# dosimeter.net
KiCad netlist of a schematic drawn in EAGLE
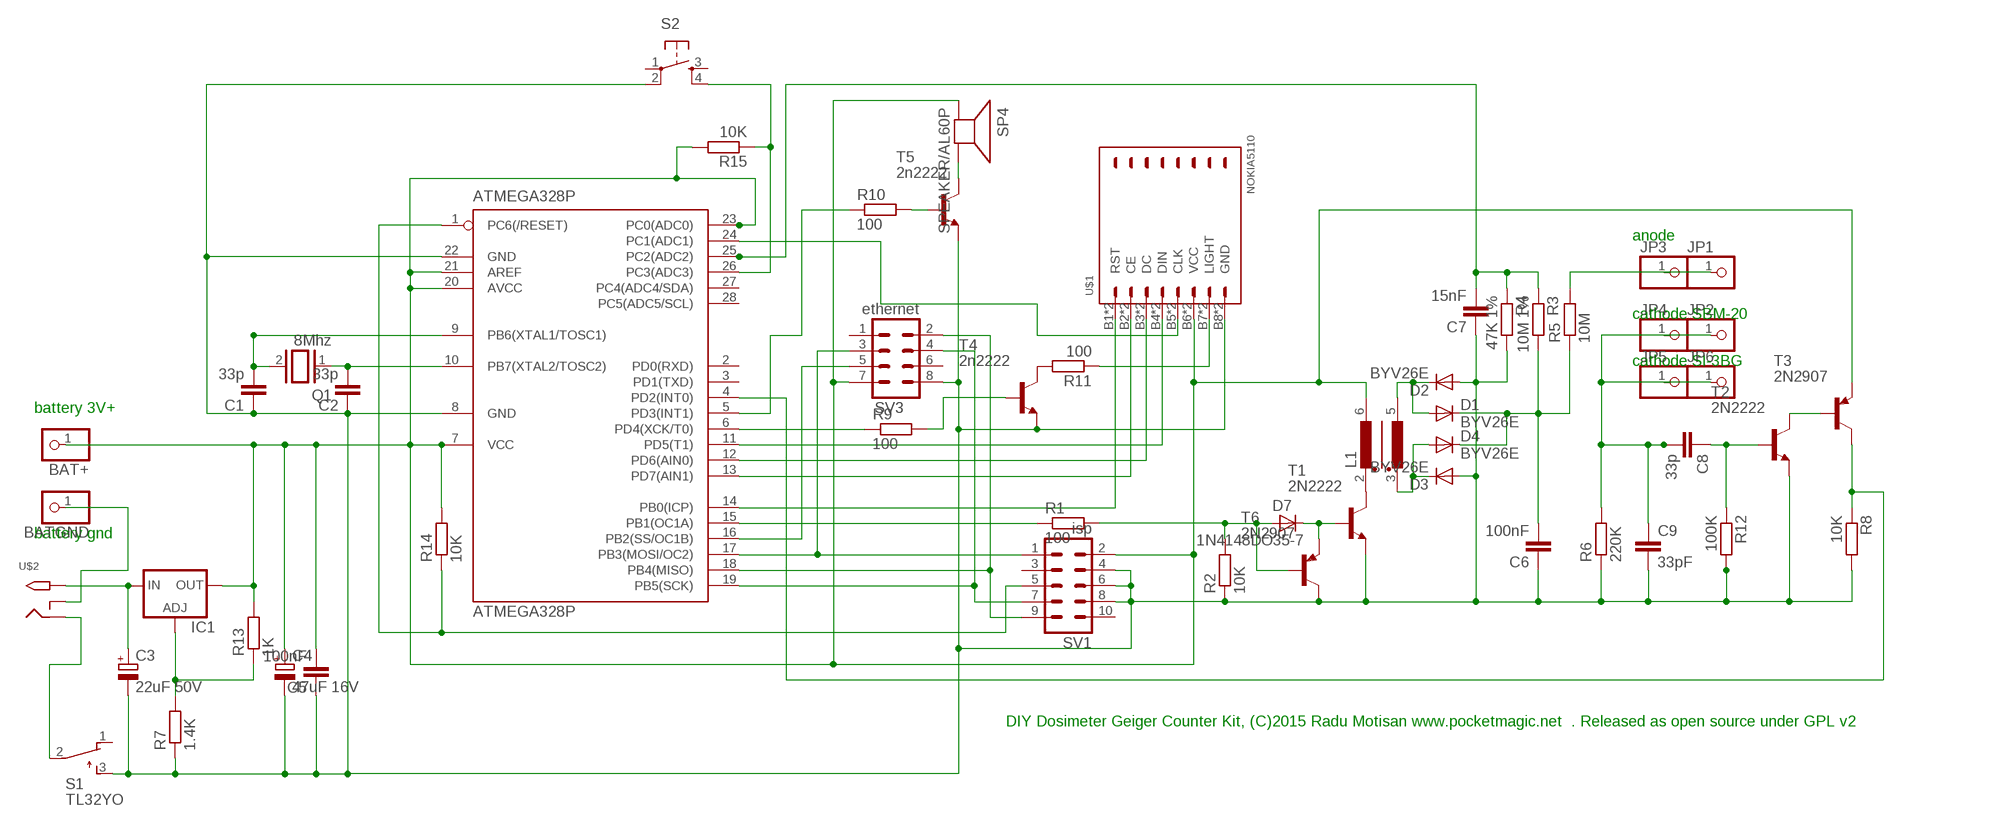
[diagram p0: schematic, sheet 1]

(export (version "E")
  (design (tool "Eeschema 10.0.6"))
  (components
    (comp (ref "ATMEGA328P")
      (value "ATMEGA328P")
      (footprint "eagle-import:DIL28-3")
      (libsource (lib "eagle-import") (part "MEGA8-P"))
    )
    (comp (ref "BAT+")
      (value "PINHD-1X1")
      (footprint "eagle-import:1X01")
      (libsource (lib "eagle-import") (part "PINHD-1X1"))
    )
    (comp (ref "BATGND")
      (value "PINHD-1X1")
      (footprint "eagle-import:1X01")
      (libsource (lib "eagle-import") (part "PINHD-1X1"))
    )
    (comp (ref "C1")
      (value "33p")
      (footprint "eagle-import:C2.5-2")
      (libsource (lib "eagle-import") (part "C2.5/2"))
    )
    (comp (ref "C2")
      (value "33p")
      (footprint "eagle-import:C2.5-2")
      (libsource (lib "eagle-import") (part "C2.5/2"))
    )
    (comp (ref "C3")
      (value "22uF 50V")
      (footprint "eagle-import:E2-5")
      (libsource (lib "eagle-import") (part "CPOL-EUE2-5"))
    )
    (comp (ref "C4")
      (value "47uF 16V")
      (footprint "eagle-import:E2-5")
      (libsource (lib "eagle-import") (part "CPOL-EUE2-5"))
    )
    (comp (ref "C5")
      (value "100nF")
      (footprint "eagle-import:C2.5-2")
      (libsource (lib "eagle-import") (part "C2.5/2"))
    )
    (comp (ref "C6")
      (value "100nF")
      (footprint "eagle-import:C5B3")
      (libsource (lib "eagle-import") (part "C5/3"))
    )
    (comp (ref "C7")
      (value "15nF")
      (footprint "eagle-import:C2.5-2")
      (libsource (lib "eagle-import") (part "C2.5/2"))
    )
    (comp (ref "C8")
      (value "33p")
      (footprint "eagle-import:C2.5-2")
      (libsource (lib "eagle-import") (part "C2.5/2"))
    )
    (comp (ref "C9")
      (value "33pF")
      (footprint "eagle-import:C2.5-2")
      (libsource (lib "eagle-import") (part "C2.5/2"))
    )
    (comp (ref "D1")
      (value "BYV26E")
      (footprint "eagle-import:D-7.5")
      (libsource (lib "eagle-import") (part "1N40047.5"))
    )
    (comp (ref "D2")
      (value "BYV26E")
      (footprint "eagle-import:D-7.5")
      (libsource (lib "eagle-import") (part "1N40047.5"))
    )
    (comp (ref "D3")
      (value "BYV26E")
      (footprint "eagle-import:D-7.5")
      (libsource (lib "eagle-import") (part "1N40047.5"))
    )
    (comp (ref "D4")
      (value "BYV26E")
      (footprint "eagle-import:D-7.5")
      (libsource (lib "eagle-import") (part "1N40047.5"))
    )
    (comp (ref "D7")
      (value "1N4148DO35-7")
      (footprint "eagle-import:DO35-7")
      (libsource (lib "eagle-import") (part "1N4148DO35-7"))
    )
    (comp (ref "IC1")
      (value "LM317TL")
      (footprint "eagle-import:317TL")
      (libsource (lib "eagle-import") (part "LM317TL"))
    )
    (comp (ref "JP1")
      (value "PINHD-1X1")
      (footprint "eagle-import:1X01")
      (libsource (lib "eagle-import") (part "PINHD-1X1"))
    )
    (comp (ref "JP2")
      (value "PINHD-1X1")
      (footprint "eagle-import:1X01")
      (libsource (lib "eagle-import") (part "PINHD-1X1"))
    )
    (comp (ref "JP3")
      (value "PINHD-1X1")
      (footprint "eagle-import:1X01")
      (libsource (lib "eagle-import") (part "PINHD-1X1"))
    )
    (comp (ref "JP4")
      (value "PINHD-1X1")
      (footprint "eagle-import:1X01")
      (libsource (lib "eagle-import") (part "PINHD-1X1"))
    )
    (comp (ref "JP5")
      (value "PINHD-1X1")
      (footprint "eagle-import:1X01")
      (libsource (lib "eagle-import") (part "PINHD-1X1"))
    )
    (comp (ref "JP6")
      (value "PINHD-1X1")
      (footprint "eagle-import:1X01")
      (libsource (lib "eagle-import") (part "PINHD-1X1"))
    )
    (comp (ref "L1")
      (value "RM6-2")
      (footprint "eagle-import:RM5-4")
      (libsource (lib "eagle-import") (part "RM6-2"))
    )
    (comp (ref "Q1")
      (value "8Mhz")
      (footprint "eagle-import:QS")
      (libsource (lib "eagle-import") (part "XTAL/S"))
    )
    (comp (ref "R1")
      (value "100")
      (footprint "eagle-import:0204_7")
      (libsource (lib "eagle-import") (part "R-EU_0204/7"))
    )
    (comp (ref "R2")
      (value "10K")
      (footprint "eagle-import:0204_7")
      (libsource (lib "eagle-import") (part "R-EU_0204/7"))
    )
    (comp (ref "R3")
      (value "10M 1%")
      (footprint "eagle-import:0204_7")
      (libsource (lib "eagle-import") (part "R-EU_0204/7"))
    )
    (comp (ref "R4")
      (value "47K 1%")
      (footprint "eagle-import:0204_7")
      (libsource (lib "eagle-import") (part "R-EU_0204/7"))
    )
    (comp (ref "R5")
      (value "10M")
      (footprint "eagle-import:0204_7")
      (libsource (lib "eagle-import") (part "R-EU_0204/7"))
    )
    (comp (ref "R6")
      (value "220K")
      (footprint "eagle-import:0204_7")
      (libsource (lib "eagle-import") (part "R-EU_0204/7"))
    )
    (comp (ref "R7")
      (value "1.4K")
      (footprint "eagle-import:0204_7")
      (libsource (lib "eagle-import") (part "R-EU_0204/7"))
    )
    (comp (ref "R8")
      (value "10K")
      (footprint "eagle-import:0204_7")
      (libsource (lib "eagle-import") (part "R-EU_0204/7"))
    )
    (comp (ref "R9")
      (value "100")
      (footprint "eagle-import:0204_7")
      (libsource (lib "eagle-import") (part "R-EU_0204/7"))
    )
    (comp (ref "R10")
      (value "100")
      (footprint "eagle-import:0204_7")
      (libsource (lib "eagle-import") (part "R-EU_0204/7"))
    )
    (comp (ref "R11")
      (value "100")
      (footprint "eagle-import:0204_7")
      (libsource (lib "eagle-import") (part "R-EU_0204/7"))
    )
    (comp (ref "R12")
      (value "100K")
      (footprint "eagle-import:0204_7")
      (libsource (lib "eagle-import") (part "R-EU_0204/7"))
    )
    (comp (ref "R13")
      (value "1K")
      (footprint "eagle-import:0204_7")
      (libsource (lib "eagle-import") (part "R-EU_0204/7"))
    )
    (comp (ref "R14")
      (value "10K")
      (footprint "eagle-import:0204_7")
      (libsource (lib "eagle-import") (part "R-EU_0204/7"))
    )
    (comp (ref "R15")
      (value "10K")
      (footprint "eagle-import:0204_7")
      (libsource (lib "eagle-import") (part "R-EU_0204/7"))
    )
    (comp (ref "S1")
      (value "TL32YO")
      (footprint "eagle-import:TL3XYO")
      (libsource (lib "eagle-import") (part "TL32YO"))
    )
    (comp (ref "S2")
      (value "TAC_SWITCHPTH")
      (footprint "eagle-import:TACTILE-PTH")
      (libsource (lib "eagle-import") (part "TAC_SWITCHPTH"))
    )
    (comp (ref "SP4")
      (value "SPEAKER/AL60P")
      (footprint "eagle-import:AL60P")
      (libsource (lib "eagle-import") (part "SPEAKER/AL60P"))
    )
    (comp (ref "SV1")
      (value "isp")
      (footprint "eagle-import:MA05-2")
      (libsource (lib "eagle-import") (part "MA05-2"))
    )
    (comp (ref "SV3")
      (value "ethernet")
      (footprint "eagle-import:MA04-2")
      (libsource (lib "eagle-import") (part "MA04-2"))
    )
    (comp (ref "T1")
      (value "2N2222")
      (footprint "eagle-import:TO92-EBC-OVAL")
      (libsource (lib "eagle-import") (part "2N2222"))
    )
    (comp (ref "T2")
      (value "2N2222")
      (footprint "eagle-import:TO92-EBC-OVAL")
      (libsource (lib "eagle-import") (part "2N2222"))
    )
    (comp (ref "T3")
      (value "2N2907")
      (footprint "eagle-import:TO92-EBC-OVAL")
      (libsource (lib "eagle-import") (part "2N2907"))
    )
    (comp (ref "T4")
      (value "2n2222")
      (footprint "eagle-import:TO92-EBC")
      (libsource (lib "eagle-import") (part "-NPN-TO92-EBC2N2222"))
    )
    (comp (ref "T5")
      (value "2n2222")
      (footprint "eagle-import:TO92-EBC")
      (libsource (lib "eagle-import") (part "-NPN-TO92-EBC2N2222"))
    )
    (comp (ref "T6")
      (value "2N2907")
      (footprint "eagle-import:TO92-EBC-OVAL")
      (libsource (lib "eagle-import") (part "2N2907"))
    )
    (comp (ref "U$1")
      (value "NOKIA5110")
      (footprint "eagle-import:NOKIA5110")
      (libsource (lib "eagle-import") (part "NOKIA5110"))
    )
    (comp (ref "U$2")
      (value "2.1MMJACKTHM")
      (footprint "eagle-import:PJ-102A")
      (libsource (lib "eagle-import") (part "2.1MMJACKTHM"))
    )
  )
  (nets
    (net (code "1") (name "Net-(ATMEGA328P-AREF)") (class "Default")
      (node (ref "ATMEGA328P") (pin "20") (pinfunction "AVCC_20") (pintype "power_in"))
      (node (ref "ATMEGA328P") (pin "21") (pinfunction "AREF_21") (pintype "passive"))
      (node (ref "ATMEGA328P") (pin "23") (pinfunction "PC0(ADC0)_23") (pintype "bidirectional"))
      (node (ref "ATMEGA328P") (pin "7") (pinfunction "VCC_7") (pintype "power_in"))
      (node (ref "BAT+") (pin "1") (pinfunction "1_1") (pintype "passive"))
      (node (ref "C4") (pin "+") (pinfunction "+_+") (pintype "passive"))
      (node (ref "C5") (pin "2") (pinfunction "2_2") (pintype "passive"))
      (node (ref "IC1") (pin "2") (pinfunction "OUT_2") (pintype "passive"))
      (node (ref "L1") (pin "6") (pinfunction "W1E_6") (pintype "passive"))
      (node (ref "R13") (pin "2") (pinfunction "2_2") (pintype "passive"))
      (node (ref "R14") (pin "2") (pinfunction "2_2") (pintype "passive"))
      (node (ref "R15") (pin "2") (pinfunction "2_2") (pintype "passive"))
      (node (ref "SP4") (pin "1") (pinfunction "+_1") (pintype "passive"))
      (node (ref "SV1") (pin "2") (pinfunction "2_2") (pintype "passive"))
      (node (ref "SV3") (pin "7") (pinfunction "7_7") (pintype "passive"))
      (node (ref "T3") (pin "E") (pinfunction "E_E") (pintype "passive"))
      (node (ref "U$1") (pin "B6") (pinfunction "VCC_B6") (pintype "bidirectional"))
      (node (ref "U$1") (pin "T6") (pinfunction "VCC_T6") (pintype "bidirectional"))
    )
    (net (code "2") (name "Net-(ATMEGA328P-PB0(ICP))") (class "Default")
      (node (ref "ATMEGA328P") (pin "14") (pinfunction "PB0(ICP)_14") (pintype "bidirectional"))
      (node (ref "U$1") (pin "B1") (pinfunction "RST_B1") (pintype "bidirectional"))
      (node (ref "U$1") (pin "T1") (pinfunction "RST_T1") (pintype "bidirectional"))
    )
    (net (code "3") (name "Net-(ATMEGA328P-PB1(OC1A))") (class "Default")
      (node (ref "ATMEGA328P") (pin "15") (pinfunction "PB1(OC1A)_15") (pintype "bidirectional"))
      (node (ref "R1") (pin "1") (pinfunction "1_1") (pintype "passive"))
    )
    (net (code "4") (name "Net-(ATMEGA328P-PB2(SS{slash}OC1B))") (class "Default")
      (node (ref "ATMEGA328P") (pin "16") (pinfunction "PB2(SS/OC1B)_16") (pintype "bidirectional"))
      (node (ref "SV3") (pin "5") (pinfunction "5_5") (pintype "passive"))
    )
    (net (code "5") (name "Net-(ATMEGA328P-PB3(MOSI{slash}OC2))") (class "Default")
      (node (ref "ATMEGA328P") (pin "17") (pinfunction "PB3(MOSI/OC2)_17") (pintype "bidirectional"))
      (node (ref "SV1") (pin "1") (pinfunction "1_1") (pintype "passive"))
      (node (ref "SV3") (pin "3") (pinfunction "3_3") (pintype "passive"))
    )
    (net (code "6") (name "Net-(ATMEGA328P-PB4(MISO))") (class "Default")
      (node (ref "ATMEGA328P") (pin "18") (pinfunction "PB4(MISO)_18") (pintype "bidirectional"))
      (node (ref "SV1") (pin "9") (pinfunction "9_9") (pintype "passive"))
      (node (ref "SV3") (pin "2") (pinfunction "2_2") (pintype "passive"))
    )
    (net (code "7") (name "Net-(ATMEGA328P-PB5(SCK))") (class "Default")
      (node (ref "ATMEGA328P") (pin "19") (pinfunction "PB5(SCK)_19") (pintype "bidirectional"))
      (node (ref "SV1") (pin "7") (pinfunction "7_7") (pintype "passive"))
      (node (ref "SV3") (pin "4") (pinfunction "4_4") (pintype "passive"))
    )
    (net (code "8") (name "Net-(ATMEGA328P-PB6(XTAL1{slash}TOSC1))") (class "Default")
      (node (ref "ATMEGA328P") (pin "9") (pinfunction "PB6(XTAL1/TOSC1)_9") (pintype "bidirectional"))
      (node (ref "C1") (pin "2") (pinfunction "2_2") (pintype "passive"))
      (node (ref "Q1") (pin "2") (pinfunction "2_2") (pintype "passive"))
    )
    (net (code "9") (name "Net-(ATMEGA328P-PB7(XTAL2{slash}TOSC2))") (class "Default")
      (node (ref "ATMEGA328P") (pin "10") (pinfunction "PB7(XTAL2/TOSC2)_10") (pintype "bidirectional"))
      (node (ref "C2") (pin "2") (pinfunction "2_2") (pintype "passive"))
      (node (ref "Q1") (pin "1") (pinfunction "1_1") (pintype "passive"))
    )
    (net (code "10") (name "Net-(ATMEGA328P-PC1(ADC1))") (class "Default")
      (node (ref "ATMEGA328P") (pin "24") (pinfunction "PC1(ADC1)_24") (pintype "bidirectional"))
      (node (ref "U$1") (pin "B5") (pinfunction "CLK_B5") (pintype "bidirectional"))
      (node (ref "U$1") (pin "T5") (pinfunction "CLK_T5") (pintype "bidirectional"))
    )
    (net (code "11") (name "Net-(ATMEGA328P-PC2(ADC2))") (class "Default")
      (node (ref "ATMEGA328P") (pin "25") (pinfunction "PC2(ADC2)_25") (pintype "bidirectional"))
      (node (ref "C7") (pin "2") (pinfunction "2_2") (pintype "passive"))
      (node (ref "R3") (pin "1") (pinfunction "1_1") (pintype "passive"))
      (node (ref "R4") (pin "1") (pinfunction "1_1") (pintype "passive"))
    )
    (net (code "12") (name "Net-(ATMEGA328P-PC3(ADC3))") (class "Default")
      (node (ref "ATMEGA328P") (pin "26") (pinfunction "PC3(ADC3)_26") (pintype "bidirectional"))
      (node (ref "R15") (pin "1") (pinfunction "1_1") (pintype "passive"))
      (node (ref "S2") (pin "4") (pinfunction "4_4") (pintype "passive"))
    )
    (net (code "13") (name "Net-(ATMEGA328P-PC6({slash}RESET))") (class "Default")
      (node (ref "ATMEGA328P") (pin "1") (pinfunction "PC6(/RESET)_1") (pintype "bidirectional"))
      (node (ref "R14") (pin "1") (pinfunction "1_1") (pintype "passive"))
      (node (ref "SV1") (pin "5") (pinfunction "5_5") (pintype "passive"))
    )
    (net (code "14") (name "Net-(ATMEGA328P-PD2(INT0))") (class "Default")
      (node (ref "ATMEGA328P") (pin "4") (pinfunction "PD2(INT0)_4") (pintype "bidirectional"))
      (node (ref "R8") (pin "1") (pinfunction "1_1") (pintype "passive"))
      (node (ref "T3") (pin "C") (pinfunction "C_C") (pintype "passive"))
    )
    (net (code "15") (name "Net-(ATMEGA328P-PD3(INT1))") (class "Default")
      (node (ref "ATMEGA328P") (pin "5") (pinfunction "PD3(INT1)_5") (pintype "bidirectional"))
      (node (ref "R10") (pin "1") (pinfunction "1_1") (pintype "passive"))
    )
    (net (code "16") (name "Net-(ATMEGA328P-PD4(XCK{slash}T0))") (class "Default")
      (node (ref "ATMEGA328P") (pin "6") (pinfunction "PD4(XCK/T0)_6") (pintype "bidirectional"))
      (node (ref "R9") (pin "1") (pinfunction "1_1") (pintype "passive"))
    )
    (net (code "17") (name "Net-(ATMEGA328P-PD5(T1))") (class "Default")
      (node (ref "ATMEGA328P") (pin "11") (pinfunction "PD5(T1)_11") (pintype "bidirectional"))
      (node (ref "U$1") (pin "B4") (pinfunction "DIN_B4") (pintype "bidirectional"))
      (node (ref "U$1") (pin "T4") (pinfunction "DIN_T4") (pintype "bidirectional"))
    )
    (net (code "18") (name "Net-(ATMEGA328P-PD6(AIN0))") (class "Default")
      (node (ref "ATMEGA328P") (pin "12") (pinfunction "PD6(AIN0)_12") (pintype "bidirectional"))
      (node (ref "U$1") (pin "B3") (pinfunction "DC_B3") (pintype "bidirectional"))
      (node (ref "U$1") (pin "T3") (pinfunction "DC_T3") (pintype "bidirectional"))
    )
    (net (code "19") (name "Net-(ATMEGA328P-PD7(AIN1))") (class "Default")
      (node (ref "ATMEGA328P") (pin "13") (pinfunction "PD7(AIN1)_13") (pintype "bidirectional"))
      (node (ref "U$1") (pin "B2") (pinfunction "CE_B2") (pintype "bidirectional"))
      (node (ref "U$1") (pin "T2") (pinfunction "CE_T2") (pintype "bidirectional"))
    )
    (net (code "20") (name "Net-(BATGND-Pad1)") (class "Default")
      (node (ref "BATGND") (pin "1") (pinfunction "1_1") (pintype "passive"))
      (node (ref "U$2") (pin "RING_SW") (pinfunction "RING_SW_RING_SW") (pintype "bidirectional"))
    )
    (net (code "21") (name "Net-(C6-Pad2)") (class "Default")
      (node (ref "C6") (pin "2") (pinfunction "2_2") (pintype "passive"))
      (node (ref "D1") (pin "C") (pinfunction "C_C") (pintype "passive"))
      (node (ref "D4") (pin "C") (pinfunction "C_C") (pintype "passive"))
      (node (ref "R3") (pin "2") (pinfunction "2_2") (pintype "passive"))
      (node (ref "R5") (pin "1") (pinfunction "1_1") (pintype "passive"))
    )
    (net (code "22") (name "Net-(C8-Pad1)") (class "Default")
      (node (ref "C8") (pin "1") (pinfunction "1_1") (pintype "passive"))
      (node (ref "R12") (pin "1") (pinfunction "1_1") (pintype "passive"))
      (node (ref "T2") (pin "B") (pinfunction "B_B") (pintype "passive"))
    )
    (net (code "23") (name "Net-(C8-Pad2)") (class "Default")
      (node (ref "C8") (pin "2") (pinfunction "2_2") (pintype "passive"))
      (node (ref "C9") (pin "1") (pinfunction "1_1") (pintype "passive"))
      (node (ref "JP2") (pin "1") (pinfunction "1_1") (pintype "passive"))
      (node (ref "JP4") (pin "1") (pinfunction "1_1") (pintype "passive"))
      (node (ref "JP5") (pin "1") (pinfunction "1_1") (pintype "passive"))
      (node (ref "JP6") (pin "1") (pinfunction "1_1") (pintype "passive"))
      (node (ref "R6") (pin "2") (pinfunction "2_2") (pintype "passive"))
    )
    (net (code "24") (name "Net-(D7-PadA)") (class "Default")
      (node (ref "D7") (pin "A") (pinfunction "A_A") (pintype "passive"))
      (node (ref "R1") (pin "2") (pinfunction "2_2") (pintype "passive"))
      (node (ref "R2") (pin "2") (pinfunction "2_2") (pintype "passive"))
      (node (ref "T6") (pin "B") (pinfunction "B_B") (pintype "passive"))
    )
    (net (code "25") (name "Net-(D7-PadC)") (class "Default")
      (node (ref "D7") (pin "C") (pinfunction "C_C") (pintype "passive"))
      (node (ref "T1") (pin "B") (pinfunction "B_B") (pintype "passive"))
      (node (ref "T6") (pin "E") (pinfunction "E_E") (pintype "passive"))
    )
    (net (code "26") (name "Net-(IC1-ADJ)") (class "Default")
      (node (ref "IC1") (pin "1") (pinfunction "ADJ_1") (pintype "input"))
      (node (ref "R13") (pin "1") (pinfunction "1_1") (pintype "passive"))
      (node (ref "R7") (pin "2") (pinfunction "2_2") (pintype "passive"))
    )
    (net (code "27") (name "Net-(IC1-IN)") (class "Default")
      (node (ref "C3") (pin "+") (pinfunction "+_+") (pintype "passive"))
      (node (ref "IC1") (pin "3") (pinfunction "IN_3") (pintype "input"))
      (node (ref "U$2") (pin "TIP") (pinfunction "TIP_TIP") (pintype "bidirectional"))
    )
    (net (code "28") (name "Net-(JP1-Pad1)") (class "Default")
      (node (ref "JP1") (pin "1") (pinfunction "1_1") (pintype "passive"))
      (node (ref "JP3") (pin "1") (pinfunction "1_1") (pintype "passive"))
      (node (ref "R5") (pin "2") (pinfunction "2_2") (pintype "passive"))
    )
    (net (code "29") (name "Net-(L1-W1A)") (class "Default")
      (node (ref "L1") (pin "2") (pinfunction "W1A_2") (pintype "passive"))
      (node (ref "T1") (pin "C") (pinfunction "C_C") (pintype "passive"))
    )
    (net (code "30") (name "Net-(L1-W2A)") (class "Default")
      (node (ref "D3") (pin "C") (pinfunction "C_C") (pintype "passive"))
      (node (ref "D4") (pin "A") (pinfunction "A_A") (pintype "passive"))
      (node (ref "L1") (pin "3") (pinfunction "W2A_3") (pintype "passive"))
    )
    (net (code "31") (name "Net-(L1-W2E)") (class "Default")
      (node (ref "D1") (pin "A") (pinfunction "A_A") (pintype "passive"))
      (node (ref "D2") (pin "C") (pinfunction "C_C") (pintype "passive"))
      (node (ref "L1") (pin "5") (pinfunction "W2E_5") (pintype "passive"))
    )
    (net (code "32") (name "Net-(R9-Pad2)") (class "Default")
      (node (ref "R9") (pin "2") (pinfunction "2_2") (pintype "passive"))
      (node (ref "T4") (pin "B") (pinfunction "B_B") (pintype "passive"))
    )
    (net (code "33") (name "Net-(R10-Pad2)") (class "Default")
      (node (ref "R10") (pin "2") (pinfunction "2_2") (pintype "passive"))
      (node (ref "T5") (pin "B") (pinfunction "B_B") (pintype "passive"))
    )
    (net (code "34") (name "Net-(R11-Pad1)") (class "Default")
      (node (ref "R11") (pin "1") (pinfunction "1_1") (pintype "passive"))
      (node (ref "U$1") (pin "B7") (pinfunction "LIGHT_B7") (pintype "bidirectional"))
      (node (ref "U$1") (pin "T7") (pinfunction "LIGHT_T7") (pintype "bidirectional"))
    )
    (net (code "35") (name "Net-(R11-Pad2)") (class "Default")
      (node (ref "R11") (pin "2") (pinfunction "2_2") (pintype "passive"))
      (node (ref "T4") (pin "C") (pinfunction "C_C") (pintype "passive"))
    )
    (net (code "36") (name "Net-(S1-P)") (class "Default")
      (node (ref "S1") (pin "2") (pinfunction "P_2") (pintype "passive"))
      (node (ref "U$2") (pin "RING") (pinfunction "RING_RING") (pintype "bidirectional"))
    )
    (net (code "37") (name "Net-(S1-S)") (class "Default")
      (node (ref "ATMEGA328P") (pin "22") (pinfunction "GND_22") (pintype "power_in"))
      (node (ref "ATMEGA328P") (pin "8") (pinfunction "GND_8") (pintype "power_in"))
      (node (ref "C1") (pin "1") (pinfunction "1_1") (pintype "passive"))
      (node (ref "C2") (pin "1") (pinfunction "1_1") (pintype "passive"))
      (node (ref "C3") (pin "-") (pinfunction "-_-") (pintype "passive"))
      (node (ref "C4") (pin "-") (pinfunction "-_-") (pintype "passive"))
      (node (ref "C5") (pin "1") (pinfunction "1_1") (pintype "passive"))
      (node (ref "C6") (pin "1") (pinfunction "1_1") (pintype "passive"))
      (node (ref "C7") (pin "1") (pinfunction "1_1") (pintype "passive"))
      (node (ref "C9") (pin "2") (pinfunction "2_2") (pintype "passive"))
      (node (ref "D2") (pin "A") (pinfunction "A_A") (pintype "passive"))
      (node (ref "D3") (pin "A") (pinfunction "A_A") (pintype "passive"))
      (node (ref "R12") (pin "2") (pinfunction "2_2") (pintype "passive"))
      (node (ref "R2") (pin "1") (pinfunction "1_1") (pintype "passive"))
      (node (ref "R4") (pin "2") (pinfunction "2_2") (pintype "passive"))
      (node (ref "R6") (pin "1") (pinfunction "1_1") (pintype "passive"))
      (node (ref "R7") (pin "1") (pinfunction "1_1") (pintype "passive"))
      (node (ref "R8") (pin "2") (pinfunction "2_2") (pintype "passive"))
      (node (ref "S1") (pin "3") (pinfunction "S_3") (pintype "passive"))
      (node (ref "S2") (pin "2") (pinfunction "2_2") (pintype "passive"))
      (node (ref "SV1") (pin "4") (pinfunction "4_4") (pintype "passive"))
      (node (ref "SV1") (pin "6") (pinfunction "6_6") (pintype "passive"))
      (node (ref "SV1") (pin "8") (pinfunction "8_8") (pintype "passive"))
      (node (ref "SV3") (pin "8") (pinfunction "8_8") (pintype "passive"))
      (node (ref "T1") (pin "E") (pinfunction "E_E") (pintype "passive"))
      (node (ref "T2") (pin "E") (pinfunction "E_E") (pintype "passive"))
      (node (ref "T4") (pin "E") (pinfunction "E_E") (pintype "passive"))
      (node (ref "T5") (pin "E") (pinfunction "E_E") (pintype "passive"))
      (node (ref "T6") (pin "C") (pinfunction "C_C") (pintype "passive"))
      (node (ref "U$1") (pin "B8") (pinfunction "GND_B8") (pintype "bidirectional"))
      (node (ref "U$1") (pin "T8") (pinfunction "GND_T8") (pintype "bidirectional"))
    )
    (net (code "38") (name "Net-(SP4--)") (class "Default")
      (node (ref "SP4") (pin "2") (pinfunction "-_2") (pintype "passive"))
      (node (ref "T5") (pin "C") (pinfunction "C_C") (pintype "passive"))
    )
    (net (code "39") (name "Net-(T2-PadC)") (class "Default")
      (node (ref "T2") (pin "C") (pinfunction "C_C") (pintype "passive"))
      (node (ref "T3") (pin "B") (pinfunction "B_B") (pintype "passive"))
    )
    (net (code "40") (name "unconnected-(ATMEGA328P-PC4(ADC4{slash}SDA)-Pad27)") (class "Default")
      (node (ref "ATMEGA328P") (pin "27") (pinfunction "PC4(ADC4/SDA)_27") (pintype "bidirectional"))
    )
    (net (code "41") (name "unconnected-(ATMEGA328P-PC5(ADC5{slash}SCL)-Pad28)") (class "Default")
      (node (ref "ATMEGA328P") (pin "28") (pinfunction "PC5(ADC5/SCL)_28") (pintype "bidirectional"))
    )
    (net (code "42") (name "unconnected-(ATMEGA328P-PD0(RXD)-Pad2)") (class "Default")
      (node (ref "ATMEGA328P") (pin "2") (pinfunction "PD0(RXD)_2") (pintype "bidirectional"))
    )
    (net (code "43") (name "unconnected-(ATMEGA328P-PD1(TXD)-Pad3)") (class "Default")
      (node (ref "ATMEGA328P") (pin "3") (pinfunction "PD1(TXD)_3") (pintype "bidirectional"))
    )
    (net (code "44") (name "unconnected-(S1-O-Pad1)") (class "Default")
      (node (ref "S1") (pin "1") (pinfunction "O_1") (pintype "passive"))
    )
    (net (code "45") (name "unconnected-(S2-Pad1)") (class "Default")
      (node (ref "S2") (pin "1") (pinfunction "1_1") (pintype "passive"))
    )
    (net (code "46") (name "unconnected-(S2-Pad3)") (class "Default")
      (node (ref "S2") (pin "3") (pinfunction "3_3") (pintype "passive"))
    )
    (net (code "47") (name "unconnected-(SV1-Pad3)") (class "Default")
      (node (ref "SV1") (pin "3") (pinfunction "3_3") (pintype "passive"))
    )
    (net (code "48") (name "unconnected-(SV1-Pad10)") (class "Default")
      (node (ref "SV1") (pin "10") (pinfunction "10_10") (pintype "passive"))
    )
    (net (code "49") (name "unconnected-(SV3-Pad1)") (class "Default")
      (node (ref "SV3") (pin "1") (pinfunction "1_1") (pintype "passive"))
    )
    (net (code "50") (name "unconnected-(SV3-Pad6)") (class "Default")
      (node (ref "SV3") (pin "6") (pinfunction "6_6") (pintype "passive"))
    )
  )
)
